# adaptateur_fusible_4N25V.net
KiCad netlist of a schematic drawn in EAGLE
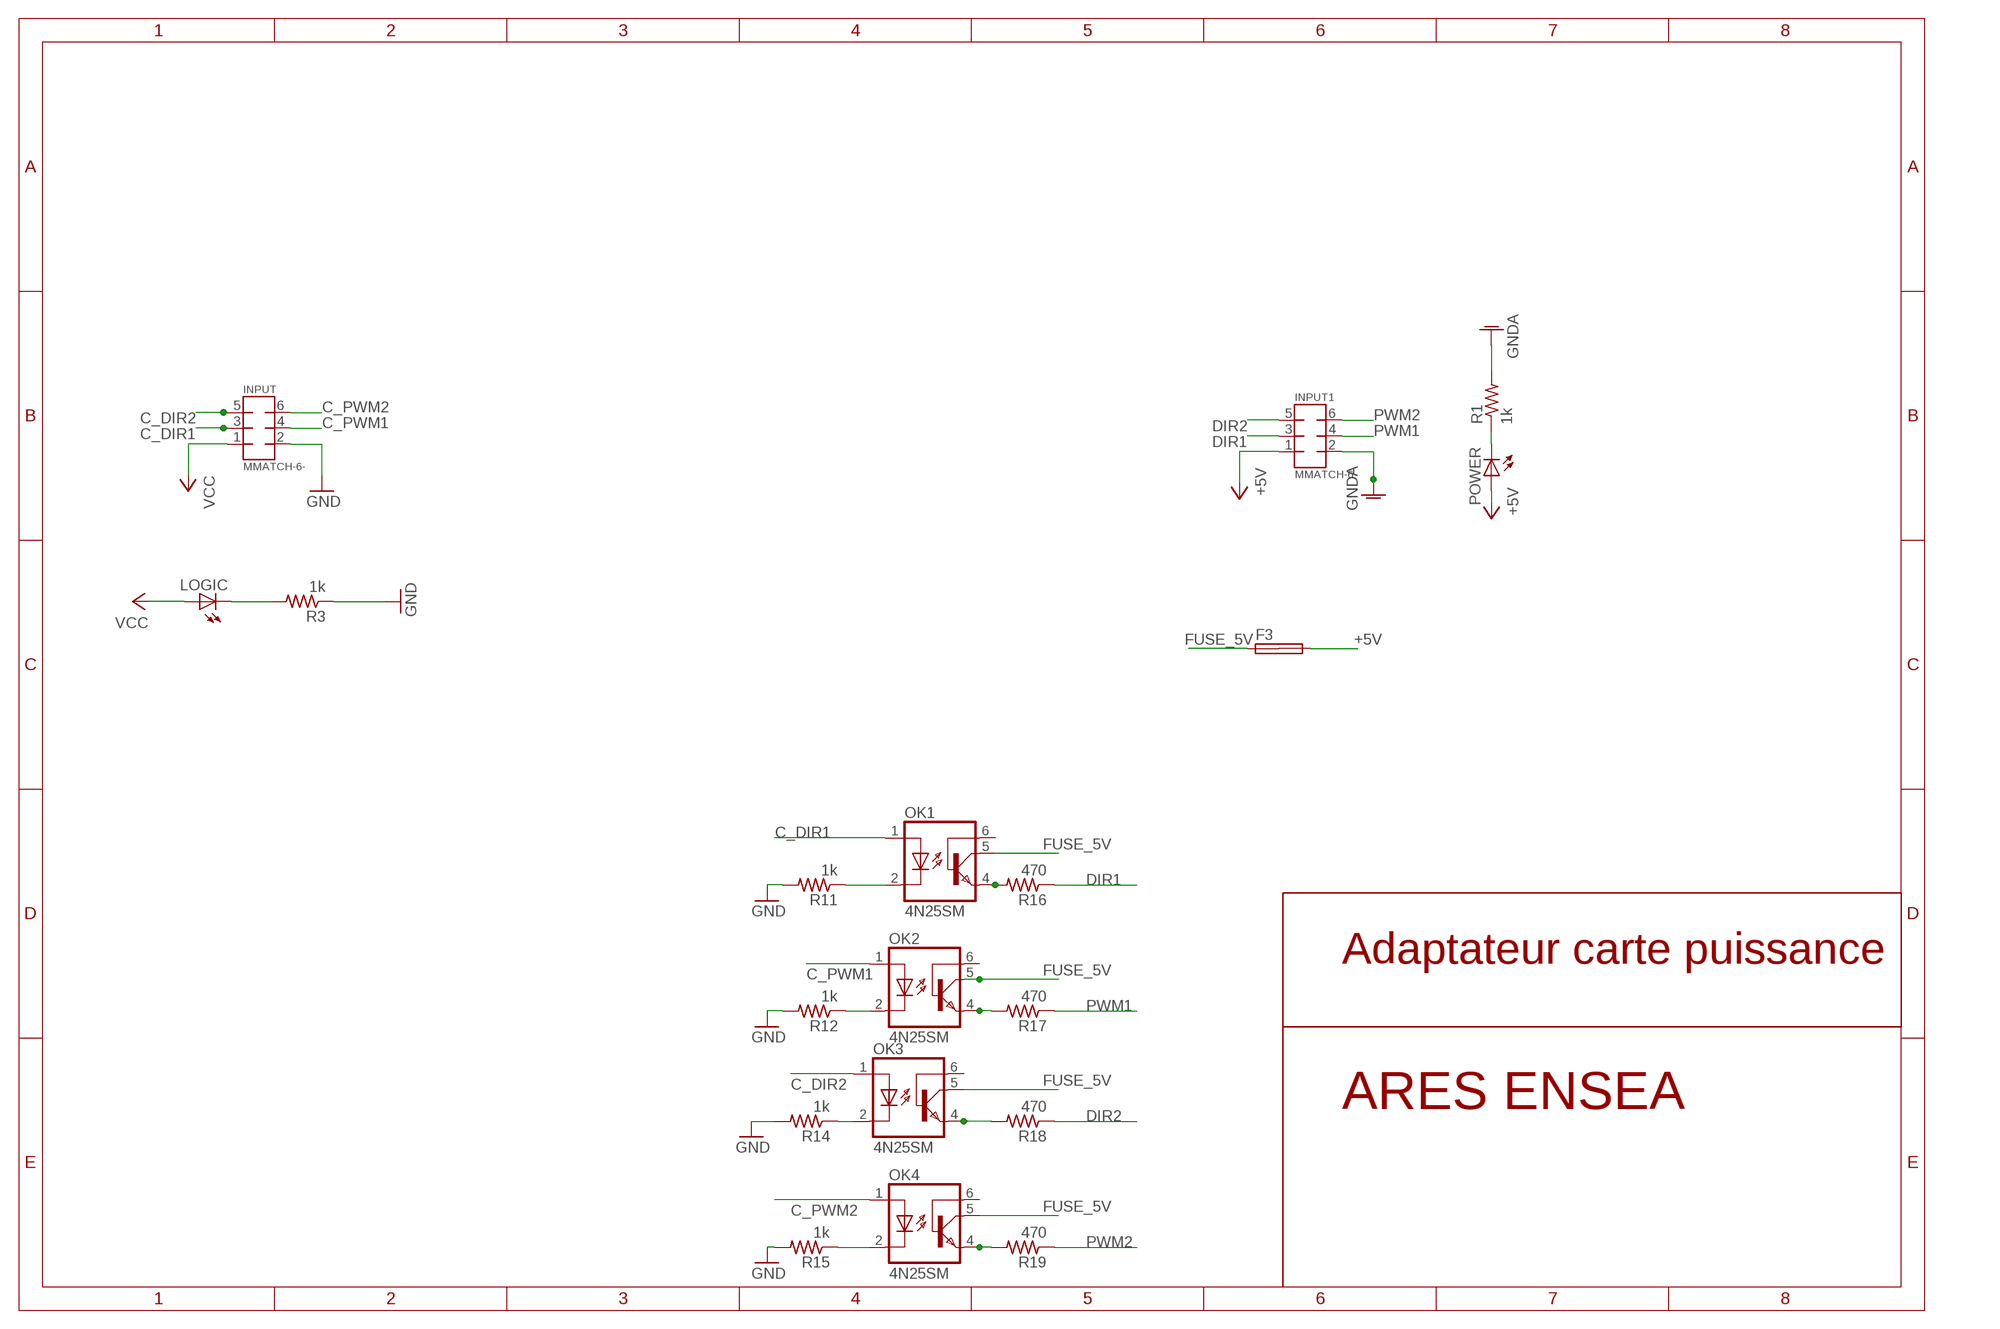
[diagram p0: schematic, sheet 1]

(export (version "E")
  (design (tool "Eeschema 10.0.6"))
  (components
    (comp (ref "F3")
      (value "SHK20L")
      (footprint "eagle-import:SHK20L")
      (libsource (lib "eagle-import") (part "SHK20L"))
    )
    (comp (ref "INPUT")
      (value "MMATCH-6-")
      (footprint "eagle-import:AMP-215079-6")
      (libsource (lib "eagle-import") (part "MMATCH-6-"))
    )
    (comp (ref "INPUT1")
      (value "MMATCH-6-")
      (footprint "eagle-import:AMP-215079-6")
      (libsource (lib "eagle-import") (part "MMATCH-6-"))
    )
    (comp (ref "LOGIC")
      (value "LEDSML0805")
      (footprint "eagle-import:SML0805")
      (libsource (lib "eagle-import") (part "LEDSML0805"))
    )
    (comp (ref "OK1")
      (value "4N25SM")
      (footprint "eagle-import:DIL6-SMD")
      (fields (field (name "MF") "FAIRCHILD SEMICONDUCTOR"))
      (libsource (lib "eagle-import") (part "4N?MS25"))
    )
    (comp (ref "OK2")
      (value "4N25SM")
      (footprint "eagle-import:DIL6-SMD")
      (fields (field (name "MF") "FAIRCHILD SEMICONDUCTOR"))
      (libsource (lib "eagle-import") (part "4N?MS25"))
    )
    (comp (ref "OK3")
      (value "4N25SM")
      (footprint "eagle-import:DIL6-SMD")
      (fields (field (name "MF") "FAIRCHILD SEMICONDUCTOR"))
      (libsource (lib "eagle-import") (part "4N?MS25"))
    )
    (comp (ref "OK4")
      (value "4N25SM")
      (footprint "eagle-import:DIL6-SMD")
      (fields (field (name "MF") "FAIRCHILD SEMICONDUCTOR"))
      (libsource (lib "eagle-import") (part "4N?MS25"))
    )
    (comp (ref "POWER")
      (value "LEDSML0805")
      (footprint "eagle-import:SML0805")
      (libsource (lib "eagle-import") (part "LEDSML0805"))
    )
    (comp (ref "R1")
      (value "1k")
      (footprint "eagle-import:M0805")
      (libsource (lib "eagle-import") (part "R-US_M0805"))
    )
    (comp (ref "R3")
      (value "1k")
      (footprint "eagle-import:M0805")
      (libsource (lib "eagle-import") (part "R-US_M0805"))
    )
    (comp (ref "R11")
      (value "1k")
      (footprint "eagle-import:M0805")
      (libsource (lib "eagle-import") (part "R-US_M0805"))
    )
    (comp (ref "R12")
      (value "1k")
      (footprint "eagle-import:M0805")
      (libsource (lib "eagle-import") (part "R-US_M0805"))
    )
    (comp (ref "R14")
      (value "1k")
      (footprint "eagle-import:M0805")
      (libsource (lib "eagle-import") (part "R-US_M0805"))
    )
    (comp (ref "R15")
      (value "1k")
      (footprint "eagle-import:M0805")
      (libsource (lib "eagle-import") (part "R-US_M0805"))
    )
    (comp (ref "R16")
      (value "470")
      (footprint "eagle-import:M0805")
      (libsource (lib "eagle-import") (part "R-US_M0805"))
    )
    (comp (ref "R17")
      (value "470")
      (footprint "eagle-import:M0805")
      (libsource (lib "eagle-import") (part "R-US_M0805"))
    )
    (comp (ref "R18")
      (value "470")
      (footprint "eagle-import:M0805")
      (libsource (lib "eagle-import") (part "R-US_M0805"))
    )
    (comp (ref "R19")
      (value "470")
      (footprint "eagle-import:M0805")
      (libsource (lib "eagle-import") (part "R-US_M0805"))
    )
  )
  (nets
    (net (code "1") (name "+5V") (class "Default")
      (node (ref "F3") (pin "2A") (pinfunction "2A_2A") (pintype "passive"))
      (node (ref "INPUT1") (pin "1") (pinfunction "3_1") (pintype "bidirectional"))
      (node (ref "POWER") (pin "A") (pinfunction "A_A") (pintype "passive"))
    )
    (net (code "2") (name "/C_DIR1") (class "Default")
      (node (ref "INPUT") (pin "3") (pinfunction "5_3") (pintype "bidirectional"))
      (node (ref "OK1") (pin "1") (pinfunction "A_1") (pintype "passive"))
    )
    (net (code "3") (name "/C_DIR2") (class "Default")
      (node (ref "INPUT") (pin "5") (pinfunction "7_5") (pintype "bidirectional"))
      (node (ref "OK3") (pin "1") (pinfunction "A_1") (pintype "passive"))
    )
    (net (code "4") (name "/C_PWM1") (class "Default")
      (node (ref "INPUT") (pin "4") (pinfunction "6_4") (pintype "bidirectional"))
      (node (ref "OK2") (pin "1") (pinfunction "A_1") (pintype "passive"))
    )
    (net (code "5") (name "/C_PWM2") (class "Default")
      (node (ref "INPUT") (pin "6") (pinfunction "8_6") (pintype "bidirectional"))
      (node (ref "OK4") (pin "1") (pinfunction "A_1") (pintype "passive"))
    )
    (net (code "6") (name "/DIR1") (class "Default")
      (node (ref "INPUT1") (pin "3") (pinfunction "5_3") (pintype "bidirectional"))
      (node (ref "R16") (pin "1") (pinfunction "1_1") (pintype "passive"))
    )
    (net (code "7") (name "/DIR2") (class "Default")
      (node (ref "INPUT1") (pin "5") (pinfunction "7_5") (pintype "bidirectional"))
      (node (ref "R18") (pin "1") (pinfunction "1_1") (pintype "passive"))
    )
    (net (code "8") (name "/FUSE_5V") (class "Default")
      (node (ref "F3") (pin "1A") (pinfunction "1A_1A") (pintype "passive"))
      (node (ref "OK1") (pin "5") (pinfunction "COL_5") (pintype "passive"))
      (node (ref "OK2") (pin "5") (pinfunction "COL_5") (pintype "passive"))
      (node (ref "OK3") (pin "5") (pinfunction "COL_5") (pintype "passive"))
      (node (ref "OK4") (pin "5") (pinfunction "COL_5") (pintype "passive"))
    )
    (net (code "9") (name "/PWM1") (class "Default")
      (node (ref "INPUT1") (pin "4") (pinfunction "6_4") (pintype "bidirectional"))
      (node (ref "R17") (pin "1") (pinfunction "1_1") (pintype "passive"))
    )
    (net (code "10") (name "/PWM2") (class "Default")
      (node (ref "INPUT1") (pin "6") (pinfunction "8_6") (pintype "bidirectional"))
      (node (ref "R19") (pin "1") (pinfunction "1_1") (pintype "passive"))
    )
    (net (code "11") (name "GND") (class "Default")
      (node (ref "INPUT") (pin "2") (pinfunction "4_2") (pintype "bidirectional"))
      (node (ref "R11") (pin "2") (pinfunction "2_2") (pintype "passive"))
      (node (ref "R12") (pin "2") (pinfunction "2_2") (pintype "passive"))
      (node (ref "R14") (pin "2") (pinfunction "2_2") (pintype "passive"))
      (node (ref "R15") (pin "2") (pinfunction "2_2") (pintype "passive"))
      (node (ref "R3") (pin "1") (pinfunction "1_1") (pintype "passive"))
    )
    (net (code "12") (name "GNDA") (class "Default")
      (node (ref "INPUT1") (pin "2") (pinfunction "4_2") (pintype "bidirectional"))
      (node (ref "R1") (pin "2") (pinfunction "2_2") (pintype "passive"))
    )
    (net (code "13") (name "Net-(LOGIC-PadC)") (class "Default")
      (node (ref "LOGIC") (pin "C") (pinfunction "C_C") (pintype "passive"))
      (node (ref "R3") (pin "2") (pinfunction "2_2") (pintype "passive"))
    )
    (net (code "14") (name "Net-(OK1-C)") (class "Default")
      (node (ref "OK1") (pin "2") (pinfunction "C_2") (pintype "passive"))
      (node (ref "R11") (pin "1") (pinfunction "1_1") (pintype "passive"))
    )
    (net (code "15") (name "Net-(OK1-EMI)") (class "Default")
      (node (ref "OK1") (pin "4") (pinfunction "EMI_4") (pintype "passive"))
      (node (ref "R16") (pin "2") (pinfunction "2_2") (pintype "passive"))
    )
    (net (code "16") (name "Net-(OK2-C)") (class "Default")
      (node (ref "OK2") (pin "2") (pinfunction "C_2") (pintype "passive"))
      (node (ref "R12") (pin "1") (pinfunction "1_1") (pintype "passive"))
    )
    (net (code "17") (name "Net-(OK2-EMI)") (class "Default")
      (node (ref "OK2") (pin "4") (pinfunction "EMI_4") (pintype "passive"))
      (node (ref "R17") (pin "2") (pinfunction "2_2") (pintype "passive"))
    )
    (net (code "18") (name "Net-(OK3-C)") (class "Default")
      (node (ref "OK3") (pin "2") (pinfunction "C_2") (pintype "passive"))
      (node (ref "R14") (pin "1") (pinfunction "1_1") (pintype "passive"))
    )
    (net (code "19") (name "Net-(OK3-EMI)") (class "Default")
      (node (ref "OK3") (pin "4") (pinfunction "EMI_4") (pintype "passive"))
      (node (ref "R18") (pin "2") (pinfunction "2_2") (pintype "passive"))
    )
    (net (code "20") (name "Net-(OK4-C)") (class "Default")
      (node (ref "OK4") (pin "2") (pinfunction "C_2") (pintype "passive"))
      (node (ref "R15") (pin "1") (pinfunction "1_1") (pintype "passive"))
    )
    (net (code "21") (name "Net-(OK4-EMI)") (class "Default")
      (node (ref "OK4") (pin "4") (pinfunction "EMI_4") (pintype "passive"))
      (node (ref "R19") (pin "2") (pinfunction "2_2") (pintype "passive"))
    )
    (net (code "22") (name "Net-(POWER-PadC)") (class "Default")
      (node (ref "POWER") (pin "C") (pinfunction "C_C") (pintype "passive"))
      (node (ref "R1") (pin "1") (pinfunction "1_1") (pintype "passive"))
    )
    (net (code "23") (name "VCC") (class "Default")
      (node (ref "INPUT") (pin "1") (pinfunction "3_1") (pintype "bidirectional"))
      (node (ref "LOGIC") (pin "A") (pinfunction "A_A") (pintype "passive"))
    )
    (net (code "24") (name "unconnected-(F3-Pad1B)") (class "Default")
      (node (ref "F3") (pin "1B") (pinfunction "1B_1B") (pintype "passive"))
    )
    (net (code "25") (name "unconnected-(F3-Pad2B)") (class "Default")
      (node (ref "F3") (pin "2B") (pinfunction "2B_2B") (pintype "passive"))
    )
    (net (code "26") (name "unconnected-(OK1-BAS-Pad6)") (class "Default")
      (node (ref "OK1") (pin "6") (pinfunction "BAS_6") (pintype "passive"))
    )
    (net (code "27") (name "unconnected-(OK2-BAS-Pad6)") (class "Default")
      (node (ref "OK2") (pin "6") (pinfunction "BAS_6") (pintype "passive"))
    )
    (net (code "28") (name "unconnected-(OK3-BAS-Pad6)") (class "Default")
      (node (ref "OK3") (pin "6") (pinfunction "BAS_6") (pintype "passive"))
    )
    (net (code "29") (name "unconnected-(OK4-BAS-Pad6)") (class "Default")
      (node (ref "OK4") (pin "6") (pinfunction "BAS_6") (pintype "passive"))
    )
  )
)
